# RGF_2_0.net
KiCad netlist of a schematic drawn in EAGLE
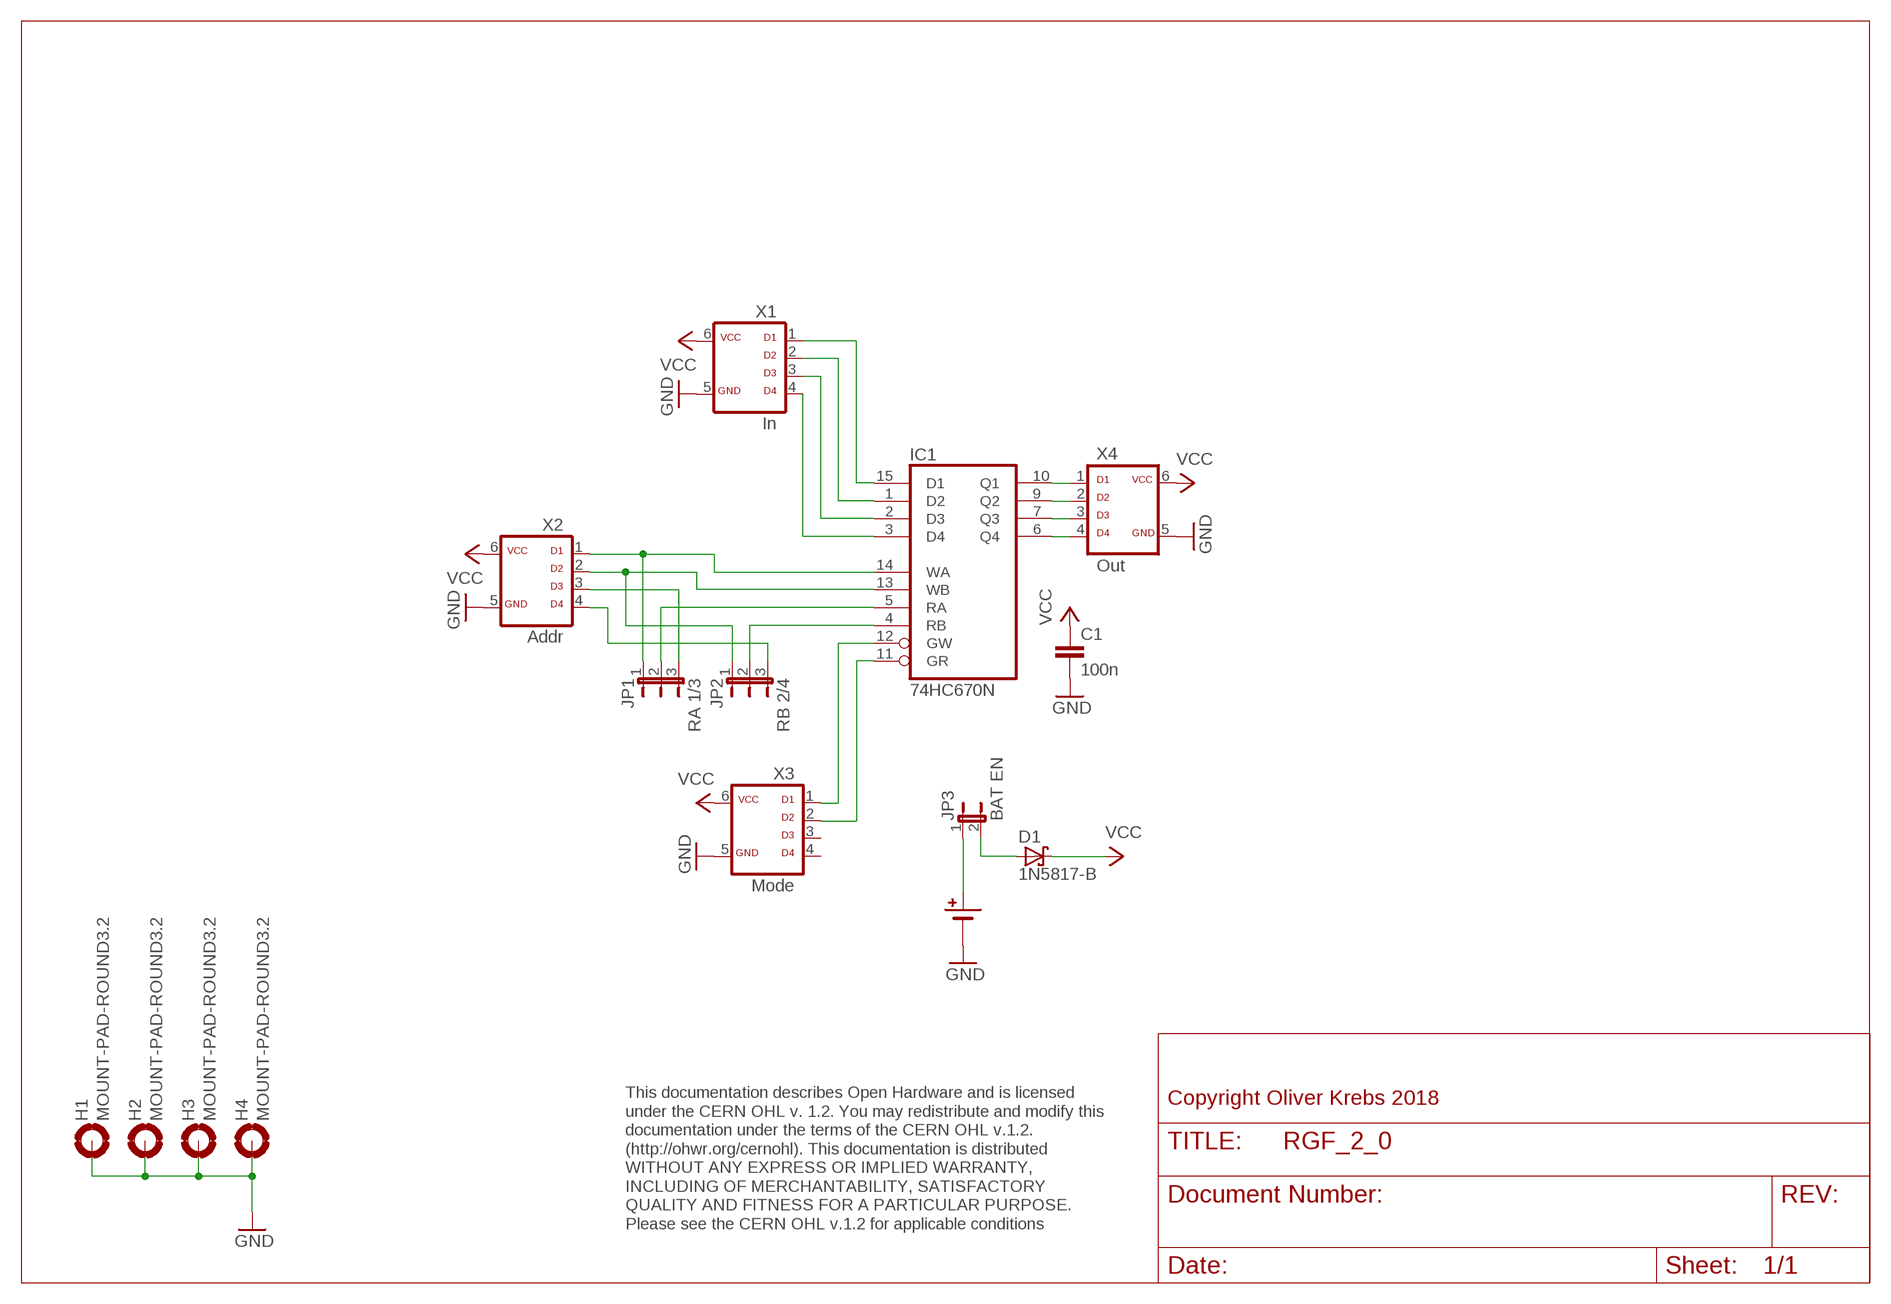
[diagram p0: schematic, sheet 1]

(export (version "E")
  (design (tool "Eeschema 10.0.6"))
  (components
    (comp (ref "C1")
      (value "100n")
      (footprint "eagle-import:C050-025X075")
      (libsource (lib "eagle-import") (part "C-EU050-025X075"))
    )
    (comp (ref "D1")
      (value "1N5817-B")
      (footprint "eagle-import:DO41-7.6")
      (libsource (lib "eagle-import") (part "1N5817-B"))
    )
    (comp (ref "H1")
      (value "MOUNT-PAD-ROUND3.2")
      (footprint "eagle-import:3,2-PAD")
      (libsource (lib "eagle-import") (part "MOUNT-PAD-ROUND3.2"))
    )
    (comp (ref "H2")
      (value "MOUNT-PAD-ROUND3.2")
      (footprint "eagle-import:3,2-PAD")
      (libsource (lib "eagle-import") (part "MOUNT-PAD-ROUND3.2"))
    )
    (comp (ref "H3")
      (value "MOUNT-PAD-ROUND3.2")
      (footprint "eagle-import:3,2-PAD")
      (libsource (lib "eagle-import") (part "MOUNT-PAD-ROUND3.2"))
    )
    (comp (ref "H4")
      (value "MOUNT-PAD-ROUND3.2")
      (footprint "eagle-import:3,2-PAD")
      (libsource (lib "eagle-import") (part "MOUNT-PAD-ROUND3.2"))
    )
    (comp (ref "IC1")
      (value "74HC670N")
      (footprint "eagle-import:DIL16")
      (libsource (lib "eagle-import") (part "74670NHC"))
    )
    (comp (ref "JP1")
      (value "RA 1/3")
      (footprint "eagle-import:JP2-U")
      (libsource (lib "eagle-import") (part "JP2EJP2-U"))
    )
    (comp (ref "JP2")
      (value "RB 2/4")
      (footprint "eagle-import:JP2-U")
      (libsource (lib "eagle-import") (part "JP2EJP2-U"))
    )
    (comp (ref "JP3")
      (value "BAT EN")
      (footprint "eagle-import:JP1")
      (libsource (lib "eagle-import") (part "JP1E"))
    )
    (comp (ref "X1")
      (value "In")
      (footprint "eagle-import:ML-6")
      (libsource (lib "eagle-import") (part "ML6D"))
    )
    (comp (ref "X2")
      (value "Addr")
      (footprint "eagle-import:ML-6")
      (libsource (lib "eagle-import") (part "ML6D"))
    )
    (comp (ref "X3")
      (value "Mode")
      (footprint "eagle-import:ML-6")
      (libsource (lib "eagle-import") (part "ML6D"))
    )
    (comp (ref "X4")
      (value "Out")
      (footprint "eagle-import:ML-6")
      (libsource (lib "eagle-import") (part "ML6D"))
    )
    (comp (ref "X5")
      (value "BATTERY")
      (footprint "eagle-import:KZH20SMD")
      (libsource (lib "eagle-import") (part "BATTERY"))
    )
  )
  (nets
    (net (code "1") (name "GND") (class "Default")
      (node (ref "C1") (pin "2") (pinfunction "2_2") (pintype "passive"))
      (node (ref "H1") (pin "B3,2") (pinfunction "MOUNT_B3,2") (pintype "passive"))
      (node (ref "H2") (pin "B3,2") (pinfunction "MOUNT_B3,2") (pintype "passive"))
      (node (ref "H3") (pin "B3,2") (pinfunction "MOUNT_B3,2") (pintype "passive"))
      (node (ref "H4") (pin "B3,2") (pinfunction "MOUNT_B3,2") (pintype "passive"))
      (node (ref "X1") (pin "5") (pinfunction "5_5") (pintype "passive"))
      (node (ref "X2") (pin "5") (pinfunction "5_5") (pintype "passive"))
      (node (ref "X3") (pin "5") (pinfunction "5_5") (pintype "passive"))
      (node (ref "X4") (pin "5") (pinfunction "5_5") (pintype "passive"))
      (node (ref "X5") (pin "N1") (pinfunction "MINUS_N1") (pintype "bidirectional"))
    )
    (net (code "2") (name "Net-(D1-PadA)") (class "Default")
      (node (ref "D1") (pin "A") (pinfunction "A_A") (pintype "passive"))
      (node (ref "JP3") (pin "2") (pinfunction "2_2") (pintype "passive"))
    )
    (net (code "3") (name "Net-(IC1A-D1)") (class "Default")
      (node (ref "IC1") (pin "15") (pinfunction "D1_15") (pintype "input"))
      (node (ref "X1") (pin "1") (pinfunction "1_1") (pintype "passive"))
    )
    (net (code "4") (name "Net-(IC1A-D2)") (class "Default")
      (node (ref "IC1") (pin "1") (pinfunction "D2_1") (pintype "input"))
      (node (ref "X1") (pin "2") (pinfunction "2_2") (pintype "passive"))
    )
    (net (code "5") (name "Net-(IC1A-D3)") (class "Default")
      (node (ref "IC1") (pin "2") (pinfunction "D3_2") (pintype "input"))
      (node (ref "X1") (pin "3") (pinfunction "3_3") (pintype "passive"))
    )
    (net (code "6") (name "Net-(IC1A-D4)") (class "Default")
      (node (ref "IC1") (pin "3") (pinfunction "D4_3") (pintype "input"))
      (node (ref "X1") (pin "4") (pinfunction "4_4") (pintype "passive"))
    )
    (net (code "7") (name "Net-(IC1A-GR)") (class "Default")
      (node (ref "IC1") (pin "11") (pinfunction "GR_11") (pintype "input"))
      (node (ref "X3") (pin "2") (pinfunction "2_2") (pintype "passive"))
    )
    (net (code "8") (name "Net-(IC1A-GW)") (class "Default")
      (node (ref "IC1") (pin "12") (pinfunction "GW_12") (pintype "input"))
      (node (ref "X3") (pin "1") (pinfunction "1_1") (pintype "passive"))
    )
    (net (code "9") (name "Net-(IC1A-Q1)") (class "Default")
      (node (ref "IC1") (pin "10") (pinfunction "Q1_10") (pintype "tri_state"))
      (node (ref "X4") (pin "1") (pinfunction "1_1") (pintype "passive"))
    )
    (net (code "10") (name "Net-(IC1A-Q2)") (class "Default")
      (node (ref "IC1") (pin "9") (pinfunction "Q2_9") (pintype "tri_state"))
      (node (ref "X4") (pin "2") (pinfunction "2_2") (pintype "passive"))
    )
    (net (code "11") (name "Net-(IC1A-Q3)") (class "Default")
      (node (ref "IC1") (pin "7") (pinfunction "Q3_7") (pintype "tri_state"))
      (node (ref "X4") (pin "3") (pinfunction "3_3") (pintype "passive"))
    )
    (net (code "12") (name "Net-(IC1A-Q4)") (class "Default")
      (node (ref "IC1") (pin "6") (pinfunction "Q4_6") (pintype "tri_state"))
      (node (ref "X4") (pin "4") (pinfunction "4_4") (pintype "passive"))
    )
    (net (code "13") (name "Net-(IC1A-RA)") (class "Default")
      (node (ref "IC1") (pin "5") (pinfunction "RA_5") (pintype "input"))
      (node (ref "JP1") (pin "2") (pinfunction "2_2") (pintype "passive"))
    )
    (net (code "14") (name "Net-(IC1A-RB)") (class "Default")
      (node (ref "IC1") (pin "4") (pinfunction "RB_4") (pintype "input"))
      (node (ref "JP2") (pin "2") (pinfunction "2_2") (pintype "passive"))
    )
    (net (code "15") (name "Net-(IC1A-WA)") (class "Default")
      (node (ref "IC1") (pin "14") (pinfunction "WA_14") (pintype "input"))
      (node (ref "JP1") (pin "1") (pinfunction "1_1") (pintype "passive"))
      (node (ref "X2") (pin "1") (pinfunction "1_1") (pintype "passive"))
    )
    (net (code "16") (name "Net-(IC1A-WB)") (class "Default")
      (node (ref "IC1") (pin "13") (pinfunction "WB_13") (pintype "input"))
      (node (ref "JP2") (pin "1") (pinfunction "1_1") (pintype "passive"))
      (node (ref "X2") (pin "2") (pinfunction "2_2") (pintype "passive"))
    )
    (net (code "17") (name "Net-(JP1-Pad3)") (class "Default")
      (node (ref "JP1") (pin "3") (pinfunction "3_3") (pintype "passive"))
      (node (ref "X2") (pin "3") (pinfunction "3_3") (pintype "passive"))
    )
    (net (code "18") (name "Net-(JP2-Pad3)") (class "Default")
      (node (ref "JP2") (pin "3") (pinfunction "3_3") (pintype "passive"))
      (node (ref "X2") (pin "4") (pinfunction "4_4") (pintype "passive"))
    )
    (net (code "19") (name "Net-(JP3-Pad1)") (class "Default")
      (node (ref "JP3") (pin "1") (pinfunction "1_1") (pintype "passive"))
      (node (ref "X5") (pin "P1") (pinfunction "PLUS_P1") (pintype "bidirectional"))
      (node (ref "X5") (pin "P2") (pinfunction "PLUS_P2") (pintype "bidirectional"))
    )
    (net (code "20") (name "VCC") (class "Default")
      (node (ref "C1") (pin "1") (pinfunction "1_1") (pintype "passive"))
      (node (ref "D1") (pin "C") (pinfunction "C_C") (pintype "passive"))
      (node (ref "X1") (pin "6") (pinfunction "6_6") (pintype "passive"))
      (node (ref "X2") (pin "6") (pinfunction "6_6") (pintype "passive"))
      (node (ref "X3") (pin "6") (pinfunction "6_6") (pintype "passive"))
      (node (ref "X4") (pin "6") (pinfunction "6_6") (pintype "passive"))
    )
    (net (code "21") (name "unconnected-(X3-Pad3)") (class "Default")
      (node (ref "X3") (pin "3") (pinfunction "3_3") (pintype "passive"))
    )
    (net (code "22") (name "unconnected-(X3-Pad4)") (class "Default")
      (node (ref "X3") (pin "4") (pinfunction "4_4") (pintype "passive"))
    )
  )
)
